# 2mono.net
KiCad netlist of a schematic drawn in EAGLE
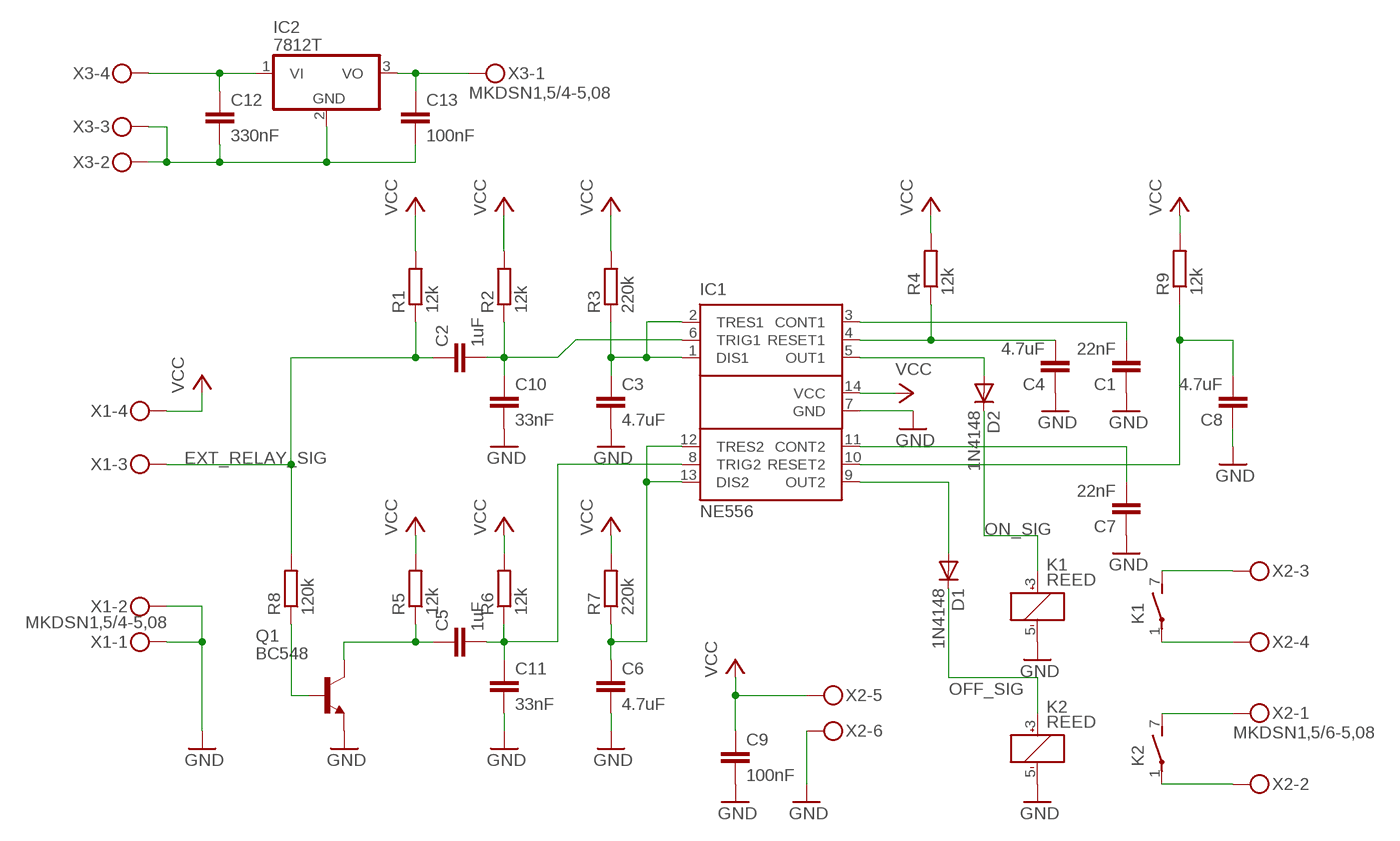
[diagram p0: schematic, sheet 1]

(export (version "E")
  (design (tool "Eeschema 10.0.6"))
  (components
    (comp (ref "C1")
      (value "22nF")
      (footprint "eagle-import:C050-025X075")
      (libsource (lib "eagle-import") (part "C-EU050-025X075"))
    )
    (comp (ref "C2")
      (value "1uF")
      (footprint "eagle-import:C025-030X050")
      (libsource (lib "eagle-import") (part "C-EU025-030X050"))
    )
    (comp (ref "C3")
      (value "4.7uF")
      (footprint "eagle-import:C025-030X050")
      (libsource (lib "eagle-import") (part "C-EU025-030X050"))
    )
    (comp (ref "C4")
      (value "4.7uF")
      (footprint "eagle-import:C025-030X050")
      (libsource (lib "eagle-import") (part "C-EU025-030X050"))
    )
    (comp (ref "C5")
      (value "1uF")
      (footprint "eagle-import:C025-030X050")
      (libsource (lib "eagle-import") (part "C-EU025-030X050"))
    )
    (comp (ref "C6")
      (value "4.7uF")
      (footprint "eagle-import:C025-030X050")
      (libsource (lib "eagle-import") (part "C-EU025-030X050"))
    )
    (comp (ref "C7")
      (value "22nF")
      (footprint "eagle-import:C050-025X075")
      (libsource (lib "eagle-import") (part "C-EU050-025X075"))
    )
    (comp (ref "C8")
      (value "4.7uF")
      (footprint "eagle-import:C025-030X050")
      (libsource (lib "eagle-import") (part "C-EU025-030X050"))
    )
    (comp (ref "C9")
      (value "100nF")
      (footprint "eagle-import:C075-042X103")
      (libsource (lib "eagle-import") (part "C-EU075-042X103"))
    )
    (comp (ref "C10")
      (value "33nF")
      (footprint "eagle-import:C050-030X075")
      (libsource (lib "eagle-import") (part "C-EU050-030X075"))
    )
    (comp (ref "C11")
      (value "33nF")
      (footprint "eagle-import:C050-030X075")
      (libsource (lib "eagle-import") (part "C-EU050-030X075"))
    )
    (comp (ref "C12")
      (value "330nF")
      (footprint "eagle-import:C075-032X103")
      (libsource (lib "eagle-import") (part "C-EU075-032X103"))
    )
    (comp (ref "C13")
      (value "100nF")
      (footprint "eagle-import:C075-042X103")
      (libsource (lib "eagle-import") (part "C-EU075-042X103"))
    )
    (comp (ref "D1")
      (value "1N4148")
      (footprint "eagle-import:DO35-10")
      (libsource (lib "eagle-import") (part "1N4148DO35-10"))
    )
    (comp (ref "D2")
      (value "1N4148")
      (footprint "eagle-import:DO35-10")
      (libsource (lib "eagle-import") (part "1N4148DO35-10"))
    )
    (comp (ref "IC1")
      (value "NE556")
      (footprint "eagle-import:DIL14")
      (libsource (lib "eagle-import") (part "NE556"))
    )
    (comp (ref "IC2")
      (value "7812T")
      (footprint "eagle-import:TO220H")
      (libsource (lib "eagle-import") (part "78T12"))
    )
    (comp (ref "K1")
      (value "REED")
      (footprint "eagle-import:REED")
      (libsource (lib "eagle-import") (part "REED"))
    )
    (comp (ref "K2")
      (value "REED")
      (footprint "eagle-import:REED")
      (libsource (lib "eagle-import") (part "REED"))
    )
    (comp (ref "Q1")
      (value "BC548")
      (footprint "eagle-import:TO92-EBC")
      (libsource (lib "eagle-import") (part "BC548"))
    )
    (comp (ref "R1")
      (value "12k")
      (footprint "eagle-import:0207_12")
      (libsource (lib "eagle-import") (part "R-EU_0207/12"))
    )
    (comp (ref "R2")
      (value "12k")
      (footprint "eagle-import:0207_12")
      (libsource (lib "eagle-import") (part "R-EU_0207/12"))
    )
    (comp (ref "R3")
      (value "220k")
      (footprint "eagle-import:0207_12")
      (libsource (lib "eagle-import") (part "R-EU_0207/12"))
    )
    (comp (ref "R4")
      (value "12k")
      (footprint "eagle-import:0207_12")
      (libsource (lib "eagle-import") (part "R-EU_0207/12"))
    )
    (comp (ref "R5")
      (value "12k")
      (footprint "eagle-import:0207_12")
      (libsource (lib "eagle-import") (part "R-EU_0207/12"))
    )
    (comp (ref "R6")
      (value "12k")
      (footprint "eagle-import:0207_12")
      (libsource (lib "eagle-import") (part "R-EU_0207/12"))
    )
    (comp (ref "R7")
      (value "220k")
      (footprint "eagle-import:0207_12")
      (libsource (lib "eagle-import") (part "R-EU_0207/12"))
    )
    (comp (ref "R8")
      (value "120k")
      (footprint "eagle-import:0207_12")
      (libsource (lib "eagle-import") (part "R-EU_0207/12"))
    )
    (comp (ref "R9")
      (value "12k")
      (footprint "eagle-import:0207_12")
      (libsource (lib "eagle-import") (part "R-EU_0207/12"))
    )
    (comp (ref "X1")
      (value "MKDSN1,5/4-5,08")
      (footprint "eagle-import:MKDSN1,5_4-5,08")
      (libsource (lib "eagle-import") (part "MKDSN1,5/4-5,08"))
    )
    (comp (ref "X2")
      (value "MKDSN1,5/6-5,08")
      (footprint "eagle-import:MKDSN1,5_6-5,08")
      (libsource (lib "eagle-import") (part "MKDSN1,5/6-5,08"))
    )
    (comp (ref "X3")
      (value "MKDSN1,5/4-5,08")
      (footprint "eagle-import:MKDSN1,5_4-5,08")
      (libsource (lib "eagle-import") (part "MKDSN1,5/4-5,08"))
    )
  )
  (nets
    (net (code "1") (name "/EXT_RELAY_SIG") (class "Default")
      (node (ref "C2") (pin "1") (pinfunction "1_1") (pintype "passive"))
      (node (ref "R1") (pin "1") (pinfunction "1_1") (pintype "passive"))
      (node (ref "R8") (pin "2") (pinfunction "2_2") (pintype "passive"))
      (node (ref "X1") (pin "3") (pinfunction "KL_3") (pintype "passive"))
    )
    (net (code "2") (name "/OFF_SIG") (class "Default")
      (node (ref "D1") (pin "C") (pinfunction "C_C") (pintype "passive"))
      (node (ref "K2") (pin "3") (pinfunction "+_3") (pintype "passive"))
    )
    (net (code "3") (name "/ON_SIG") (class "Default")
      (node (ref "D2") (pin "C") (pinfunction "C_C") (pintype "passive"))
      (node (ref "K1") (pin "3") (pinfunction "+_3") (pintype "passive"))
    )
    (net (code "4") (name "GND") (class "Default")
      (node (ref "C1") (pin "1") (pinfunction "1_1") (pintype "passive"))
      (node (ref "C10") (pin "2") (pinfunction "2_2") (pintype "passive"))
      (node (ref "C11") (pin "2") (pinfunction "2_2") (pintype "passive"))
      (node (ref "C3") (pin "2") (pinfunction "2_2") (pintype "passive"))
      (node (ref "C4") (pin "1") (pinfunction "1_1") (pintype "passive"))
      (node (ref "C6") (pin "2") (pinfunction "2_2") (pintype "passive"))
      (node (ref "C7") (pin "1") (pinfunction "1_1") (pintype "passive"))
      (node (ref "C8") (pin "1") (pinfunction "1_1") (pintype "passive"))
      (node (ref "C9") (pin "2") (pinfunction "2_2") (pintype "passive"))
      (node (ref "IC1") (pin "7") (pinfunction "GND_7") (pintype "power_in"))
      (node (ref "K1") (pin "5") (pinfunction "-_5") (pintype "passive"))
      (node (ref "K2") (pin "5") (pinfunction "-_5") (pintype "passive"))
      (node (ref "Q1") (pin "E") (pinfunction "E_E") (pintype "passive"))
      (node (ref "X1") (pin "1") (pinfunction "KL_1") (pintype "passive"))
      (node (ref "X1") (pin "2") (pinfunction "KL_2") (pintype "passive"))
      (node (ref "X2") (pin "6") (pinfunction "KL_6") (pintype "passive"))
    )
    (net (code "5") (name "Net-(C5-Pad1)") (class "Default")
      (node (ref "C5") (pin "1") (pinfunction "1_1") (pintype "passive"))
      (node (ref "Q1") (pin "C") (pinfunction "C_C") (pintype "passive"))
      (node (ref "R5") (pin "1") (pinfunction "1_1") (pintype "passive"))
    )
    (net (code "6") (name "Net-(IC1-CONT1)") (class "Default")
      (node (ref "C1") (pin "2") (pinfunction "2_2") (pintype "passive"))
      (node (ref "IC1") (pin "3") (pinfunction "CONT1_3") (pintype "input"))
    )
    (net (code "7") (name "Net-(IC1-CONT2)") (class "Default")
      (node (ref "C7") (pin "2") (pinfunction "2_2") (pintype "passive"))
      (node (ref "IC1") (pin "11") (pinfunction "CONT2_11") (pintype "input"))
    )
    (net (code "8") (name "Net-(IC1-DIS1)") (class "Default")
      (node (ref "C3") (pin "1") (pinfunction "1_1") (pintype "passive"))
      (node (ref "IC1") (pin "1") (pinfunction "DIS1_1") (pintype "input"))
      (node (ref "IC1") (pin "2") (pinfunction "TRES1_2") (pintype "input"))
      (node (ref "R3") (pin "1") (pinfunction "1_1") (pintype "passive"))
    )
    (net (code "9") (name "Net-(IC1-DIS2)") (class "Default")
      (node (ref "C6") (pin "1") (pinfunction "1_1") (pintype "passive"))
      (node (ref "IC1") (pin "12") (pinfunction "TRES2_12") (pintype "input"))
      (node (ref "IC1") (pin "13") (pinfunction "DIS2_13") (pintype "input"))
      (node (ref "R7") (pin "1") (pinfunction "1_1") (pintype "passive"))
    )
    (net (code "10") (name "Net-(IC1-OUT1)") (class "Default")
      (node (ref "D2") (pin "A") (pinfunction "A_A") (pintype "passive"))
      (node (ref "IC1") (pin "5") (pinfunction "OUT1_5") (pintype "output"))
    )
    (net (code "11") (name "Net-(IC1-OUT2)") (class "Default")
      (node (ref "D1") (pin "A") (pinfunction "A_A") (pintype "passive"))
      (node (ref "IC1") (pin "9") (pinfunction "OUT2_9") (pintype "output"))
    )
    (net (code "12") (name "Net-(IC1-RESET1)") (class "Default")
      (node (ref "C4") (pin "2") (pinfunction "2_2") (pintype "passive"))
      (node (ref "IC1") (pin "4") (pinfunction "RESET1_4") (pintype "input"))
      (node (ref "R4") (pin "1") (pinfunction "1_1") (pintype "passive"))
    )
    (net (code "13") (name "Net-(IC1-RESET2)") (class "Default")
      (node (ref "C8") (pin "2") (pinfunction "2_2") (pintype "passive"))
      (node (ref "IC1") (pin "10") (pinfunction "RESET2_10") (pintype "input"))
      (node (ref "R9") (pin "1") (pinfunction "1_1") (pintype "passive"))
    )
    (net (code "14") (name "Net-(IC1-TRIG1)") (class "Default")
      (node (ref "C10") (pin "1") (pinfunction "1_1") (pintype "passive"))
      (node (ref "C2") (pin "2") (pinfunction "2_2") (pintype "passive"))
      (node (ref "IC1") (pin "6") (pinfunction "TRIG1_6") (pintype "input"))
      (node (ref "R2") (pin "1") (pinfunction "1_1") (pintype "passive"))
    )
    (net (code "15") (name "Net-(IC1-TRIG2)") (class "Default")
      (node (ref "C11") (pin "1") (pinfunction "1_1") (pintype "passive"))
      (node (ref "C5") (pin "2") (pinfunction "2_2") (pintype "passive"))
      (node (ref "IC1") (pin "8") (pinfunction "TRIG2_8") (pintype "input"))
      (node (ref "R6") (pin "1") (pinfunction "1_1") (pintype "passive"))
    )
    (net (code "16") (name "Net-(IC2-GND)") (class "Default")
      (node (ref "C12") (pin "2") (pinfunction "2_2") (pintype "passive"))
      (node (ref "C13") (pin "2") (pinfunction "2_2") (pintype "passive"))
      (node (ref "IC2") (pin "2") (pinfunction "GND_2") (pintype "passive"))
      (node (ref "X3") (pin "2") (pinfunction "KL_2") (pintype "passive"))
      (node (ref "X3") (pin "3") (pinfunction "KL_3") (pintype "passive"))
    )
    (net (code "17") (name "Net-(IC2-VI)") (class "Default")
      (node (ref "C12") (pin "1") (pinfunction "1_1") (pintype "passive"))
      (node (ref "IC2") (pin "1") (pinfunction "VI_1") (pintype "input"))
      (node (ref "X3") (pin "4") (pinfunction "KL_4") (pintype "passive"))
    )
    (net (code "18") (name "Net-(IC2-VO)") (class "Default")
      (node (ref "C13") (pin "1") (pinfunction "1_1") (pintype "passive"))
      (node (ref "IC2") (pin "3") (pinfunction "VO_3") (pintype "passive"))
      (node (ref "X3") (pin "1") (pinfunction "KL_1") (pintype "passive"))
    )
    (net (code "19") (name "Net-(K1B-P)") (class "Default")
      (node (ref "K1") (pin "1") (pinfunction "P_1") (pintype "passive"))
      (node (ref "X2") (pin "4") (pinfunction "KL_4") (pintype "passive"))
    )
    (net (code "20") (name "Net-(K1B-S)") (class "Default")
      (node (ref "K1") (pin "7") (pinfunction "S_7") (pintype "passive"))
      (node (ref "X2") (pin "3") (pinfunction "KL_3") (pintype "passive"))
    )
    (net (code "21") (name "Net-(K2B-P)") (class "Default")
      (node (ref "K2") (pin "1") (pinfunction "P_1") (pintype "passive"))
      (node (ref "X2") (pin "2") (pinfunction "KL_2") (pintype "passive"))
    )
    (net (code "22") (name "Net-(K2B-S)") (class "Default")
      (node (ref "K2") (pin "7") (pinfunction "S_7") (pintype "passive"))
      (node (ref "X2") (pin "1") (pinfunction "KL_1") (pintype "passive"))
    )
    (net (code "23") (name "Net-(Q1-PadB)") (class "Default")
      (node (ref "Q1") (pin "B") (pinfunction "B_B") (pintype "passive"))
      (node (ref "R8") (pin "1") (pinfunction "1_1") (pintype "passive"))
    )
    (net (code "24") (name "VCC") (class "Default")
      (node (ref "C9") (pin "1") (pinfunction "1_1") (pintype "passive"))
      (node (ref "IC1") (pin "14") (pinfunction "VCC_14") (pintype "power_in"))
      (node (ref "R1") (pin "2") (pinfunction "2_2") (pintype "passive"))
      (node (ref "R2") (pin "2") (pinfunction "2_2") (pintype "passive"))
      (node (ref "R3") (pin "2") (pinfunction "2_2") (pintype "passive"))
      (node (ref "R4") (pin "2") (pinfunction "2_2") (pintype "passive"))
      (node (ref "R5") (pin "2") (pinfunction "2_2") (pintype "passive"))
      (node (ref "R6") (pin "2") (pinfunction "2_2") (pintype "passive"))
      (node (ref "R7") (pin "2") (pinfunction "2_2") (pintype "passive"))
      (node (ref "R9") (pin "2") (pinfunction "2_2") (pintype "passive"))
      (node (ref "X1") (pin "4") (pinfunction "KL_4") (pintype "passive"))
      (node (ref "X2") (pin "5") (pinfunction "KL_5") (pintype "passive"))
    )
  )
)
